# alimentation.net
KiCad netlist of a schematic drawn in Altium Designer
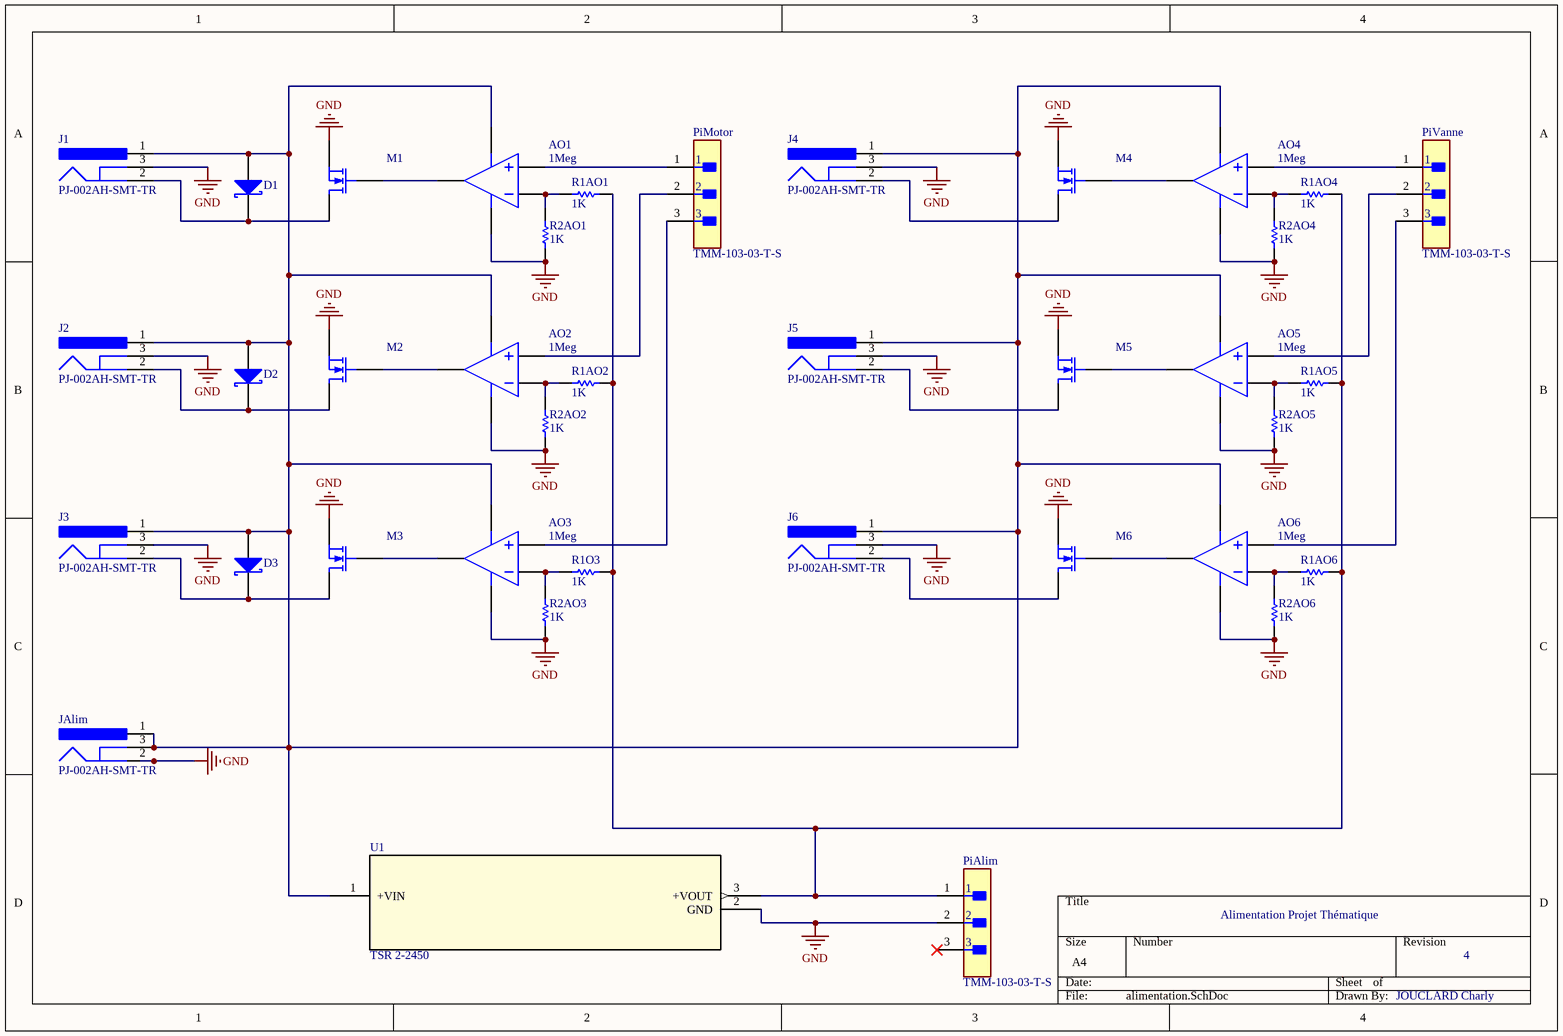
[diagram p0: alimentation.SchDoc]

(export (version "E")
  (design (tool "Eeschema 10.0.6"))
  (components
    (comp (ref "AO1")
      (value "Ideal Operational Amplifier")
      (fields (field (name "GAIN") "1Meg"))
      (libsource (lib "Simulation Generic Components") (part "OpAmp with power terminals"))
    )
    (comp (ref "AO2")
      (value "Ideal Operational Amplifier")
      (fields (field (name "GAIN") "1Meg"))
      (libsource (lib "Simulation Generic Components") (part "OpAmp with power terminals"))
    )
    (comp (ref "AO3")
      (value "Ideal Operational Amplifier")
      (fields (field (name "GAIN") "1Meg"))
      (libsource (lib "Simulation Generic Components") (part "OpAmp with power terminals"))
    )
    (comp (ref "AO4")
      (value "Ideal Operational Amplifier")
      (fields (field (name "GAIN") "1Meg"))
      (libsource (lib "Simulation Generic Components") (part "OpAmp with power terminals"))
    )
    (comp (ref "AO5")
      (value "Ideal Operational Amplifier")
      (fields (field (name "GAIN") "1Meg"))
      (libsource (lib "Simulation Generic Components") (part "OpAmp with power terminals"))
    )
    (comp (ref "AO6")
      (value "Ideal Operational Amplifier")
      (fields (field (name "GAIN") "1Meg"))
      (libsource (lib "Simulation Generic Components") (part "OpAmp with power terminals"))
    )
    (comp (ref "D1")
      (value "Shottky Diode")
      (libsource (lib "Simulation Generic Components") (part "Shottky Diode"))
    )
    (comp (ref "D2")
      (value "Shottky Diode")
      (libsource (lib "Simulation Generic Components") (part "Shottky Diode"))
    )
    (comp (ref "D3")
      (value "Shottky Diode")
      (libsource (lib "Simulation Generic Components") (part "Shottky Diode"))
    )
    (comp (ref "J1")
      (value "PJ-002AH-SMT-TR")
      (footprint "CUI-PJ-002AH-4_V")
      (description "DC Power Jack, Right Angle, -25 to 85 degC, 4-Pin 14.8 x 9 x 11 mm SMD, RoHS, Tape and Reel")
      (fields (field (name "MANUFACTURER") "CUIInc.") (field (name "PARTNUMBER") "PJ-002AH"))
      (libsource (lib "Altium Content Vault") (part "JACK-2CD3-RN_B"))
    )
    (comp (ref "J2")
      (value "PJ-002AH-SMT-TR")
      (footprint "CUI-PJ-002AH-4_V")
      (description "DC Power Jack, Right Angle, -25 to 85 degC, 4-Pin 14.8 x 9 x 11 mm SMD, RoHS, Tape and Reel")
      (fields (field (name "MANUFACTURER") "CUIInc.") (field (name "PARTNUMBER") "PJ-002AH"))
      (libsource (lib "Altium Content Vault") (part "JACK-2CD3-RN_B"))
    )
    (comp (ref "J3")
      (value "PJ-002AH-SMT-TR")
      (footprint "CUI-PJ-002AH-4_V")
      (description "DC Power Jack, Right Angle, -25 to 85 degC, 4-Pin 14.8 x 9 x 11 mm SMD, RoHS, Tape and Reel")
      (fields (field (name "MANUFACTURER") "CUIInc.") (field (name "PARTNUMBER") "PJ-002AH"))
      (libsource (lib "Altium Content Vault") (part "JACK-2CD3-RN_B"))
    )
    (comp (ref "J4")
      (value "PJ-002AH-SMT-TR")
      (footprint "CUI-PJ-002AH-4_V")
      (description "DC Power Jack, Right Angle, -25 to 85 degC, 4-Pin 14.8 x 9 x 11 mm SMD, RoHS, Tape and Reel")
      (fields (field (name "MANUFACTURER") "CUIInc.") (field (name "PARTNUMBER") "PJ-002AH"))
      (libsource (lib "Altium Content Vault") (part "JACK-2CD3-RN_B"))
    )
    (comp (ref "J5")
      (value "PJ-002AH-SMT-TR")
      (footprint "CUI-PJ-002AH-4_V")
      (description "DC Power Jack, Right Angle, -25 to 85 degC, 4-Pin 14.8 x 9 x 11 mm SMD, RoHS, Tape and Reel")
      (fields (field (name "MANUFACTURER") "CUIInc.") (field (name "PARTNUMBER") "PJ-002AH"))
      (libsource (lib "Altium Content Vault") (part "JACK-2CD3-RN_B"))
    )
    (comp (ref "J6")
      (value "PJ-002AH-SMT-TR")
      (footprint "CUI-PJ-002AH-4_V")
      (description "DC Power Jack, Right Angle, -25 to 85 degC, 4-Pin 14.8 x 9 x 11 mm SMD, RoHS, Tape and Reel")
      (fields (field (name "MANUFACTURER") "CUIInc.") (field (name "PARTNUMBER") "PJ-002AH"))
      (libsource (lib "Altium Content Vault") (part "JACK-2CD3-RN_B"))
    )
    (comp (ref "JAlim")
      (value "PJ-002AH-SMT-TR")
      (footprint "CUI-PJ-002AH-4_V")
      (description "DC Power Jack, Right Angle, -25 to 85 degC, 4-Pin 14.8 x 9 x 11 mm SMD, RoHS, Tape and Reel")
      (fields (field (name "MANUFACTURER") "CUIInc.") (field (name "PARTNUMBER") "PJ-002AH"))
      (libsource (lib "Altium Content Vault") (part "JACK-2CD3-RN_B"))
    )
    (comp (ref "M1")
      (value "N-chanel Power MOSFET VDMOS Model")
      (description "MOSFET CSD18537NKCS")
      (libsource (lib "Simulation Generic Components") (part "MOSFET N-ch VDMOS"))
    )
    (comp (ref "M2")
      (value "N-chanel Power MOSFET VDMOS Model")
      (description "MOSFET CSD18537NKCS")
      (libsource (lib "Simulation Generic Components") (part "MOSFET N-ch VDMOS"))
    )
    (comp (ref "M3")
      (value "N-chanel Power MOSFET VDMOS Model")
      (description "MOSFET CSD18537NKCS")
      (libsource (lib "Simulation Generic Components") (part "MOSFET N-ch VDMOS"))
    )
    (comp (ref "M4")
      (value "N-chanel Power MOSFET VDMOS Model")
      (description "MOSFET CSD18537NKCS")
      (libsource (lib "Simulation Generic Components") (part "MOSFET N-ch VDMOS"))
    )
    (comp (ref "M5")
      (value "N-chanel Power MOSFET VDMOS Model")
      (description "MOSFET CSD18537NKCS")
      (libsource (lib "Simulation Generic Components") (part "MOSFET N-ch VDMOS"))
    )
    (comp (ref "M6")
      (value "N-chanel Power MOSFET VDMOS Model")
      (description "MOSFET CSD18537NKCS")
      (libsource (lib "Simulation Generic Components") (part "MOSFET N-ch VDMOS"))
    )
    (comp (ref "PiAlim")
      (value "TMM-103-03-T-S")
      (footprint "FP-TMM-103-03-T-S-MFG")
      (description "CONN HEADER VERT 3POS 2MM")
      (libsource (lib "Altium Content Vault") (part "0d3f023dd272f625e17a2be33dea85f"))
    )
    (comp (ref "PiMotor")
      (value "TMM-103-03-T-S")
      (footprint "FP-TMM-103-03-T-S-MFG")
      (description "CONN HEADER VERT 3POS 2MM")
      (libsource (lib "Altium Content Vault") (part "0d3f023dd272f625e17a2be33dea85f"))
    )
    (comp (ref "PiVanne")
      (value "TMM-103-03-T-S")
      (footprint "FP-TMM-103-03-T-S-MFG")
      (description "CONN HEADER VERT 3POS 2MM")
      (libsource (lib "Altium Content Vault") (part "0d3f023dd272f625e17a2be33dea85f"))
    )
    (comp (ref "R1AO1")
      (value "1K")
      (description "Resistor")
      (libsource (lib "Simulation Generic Components") (part "Resistor"))
    )
    (comp (ref "R1AO2")
      (value "1K")
      (description "Resistor")
      (libsource (lib "Simulation Generic Components") (part "Resistor"))
    )
    (comp (ref "R1AO4")
      (value "1K")
      (description "Resistor")
      (libsource (lib "Simulation Generic Components") (part "Resistor"))
    )
    (comp (ref "R1AO5")
      (value "1K")
      (description "Resistor")
      (libsource (lib "Simulation Generic Components") (part "Resistor"))
    )
    (comp (ref "R1AO6")
      (value "1K")
      (description "Resistor")
      (libsource (lib "Simulation Generic Components") (part "Resistor"))
    )
    (comp (ref "R1O3")
      (value "1K")
      (description "Resistor")
      (libsource (lib "Simulation Generic Components") (part "Resistor"))
    )
    (comp (ref "R2AO1")
      (value "1K")
      (description "Resistor")
      (libsource (lib "Simulation Generic Components") (part "Resistor"))
    )
    (comp (ref "R2AO2")
      (value "1K")
      (description "Resistor")
      (libsource (lib "Simulation Generic Components") (part "Resistor"))
    )
    (comp (ref "R2AO3")
      (value "1K")
      (description "Resistor")
      (libsource (lib "Simulation Generic Components") (part "Resistor"))
    )
    (comp (ref "R2AO4")
      (value "1K")
      (description "Resistor")
      (libsource (lib "Simulation Generic Components") (part "Resistor"))
    )
    (comp (ref "R2AO5")
      (value "1K")
      (description "Resistor")
      (libsource (lib "Simulation Generic Components") (part "Resistor"))
    )
    (comp (ref "R2AO6")
      (value "1K")
      (description "Resistor")
      (libsource (lib "Simulation Generic Components") (part "Resistor"))
    )
    (comp (ref "U1")
      (value "TSR 2-2450")
      (footprint "TSR 2-2450_TRP")
      (description "DC DC CONVERTER 5V 10W")
      (libsource (lib "Altium Content Vault") (part "TSR 2-2450"))
    )
  )
  (nets
    (net (code "1") (name "GND") (class "Default")
      (node (ref "AO1") (pin "4") (pinfunction "V+_4") (pintype "power_in"))
      (node (ref "AO2") (pin "4") (pinfunction "V+_4") (pintype "power_in"))
      (node (ref "AO3") (pin "4") (pinfunction "V+_4") (pintype "power_in"))
      (node (ref "AO4") (pin "4") (pinfunction "V+_4") (pintype "power_in"))
      (node (ref "AO5") (pin "4") (pinfunction "V+_4") (pintype "power_in"))
      (node (ref "AO6") (pin "4") (pinfunction "V+_4") (pintype "power_in"))
      (node (ref "J1") (pin "3") (pinfunction "3_3") (pintype "passive"))
      (node (ref "J2") (pin "3") (pinfunction "3_3") (pintype "passive"))
      (node (ref "J3") (pin "3") (pinfunction "3_3") (pintype "passive"))
      (node (ref "J4") (pin "3") (pinfunction "3_3") (pintype "passive"))
      (node (ref "J5") (pin "3") (pinfunction "3_3") (pintype "passive"))
      (node (ref "J6") (pin "3") (pinfunction "3_3") (pintype "passive"))
      (node (ref "JAlim") (pin "2") (pinfunction "2_2") (pintype "passive"))
      (node (ref "M1") (pin "3") (pinfunction "S_3") (pintype "passive"))
      (node (ref "M2") (pin "3") (pinfunction "S_3") (pintype "passive"))
      (node (ref "M3") (pin "3") (pinfunction "S_3") (pintype "passive"))
      (node (ref "M4") (pin "3") (pinfunction "S_3") (pintype "passive"))
      (node (ref "M5") (pin "3") (pinfunction "S_3") (pintype "passive"))
      (node (ref "M6") (pin "3") (pinfunction "S_3") (pintype "passive"))
      (node (ref "PiAlim") (pin "2") (pinfunction "2_2") (pintype "passive"))
      (node (ref "R2AO1") (pin "1") (pinfunction "1_1") (pintype "passive"))
      (node (ref "R2AO2") (pin "1") (pinfunction "1_1") (pintype "passive"))
      (node (ref "R2AO3") (pin "1") (pinfunction "1_1") (pintype "passive"))
      (node (ref "R2AO4") (pin "1") (pinfunction "1_1") (pintype "passive"))
      (node (ref "R2AO5") (pin "1") (pinfunction "1_1") (pintype "passive"))
      (node (ref "R2AO6") (pin "1") (pinfunction "1_1") (pintype "passive"))
      (node (ref "U1") (pin "2") (pinfunction "GND_2") (pintype "power_in"))
    )
    (net (code "2") (name "Net-(AO1-IN+)") (class "Default")
      (node (ref "AO1") (pin "2") (pinfunction "IN+_2") (pintype "passive"))
      (node (ref "PiMotor") (pin "1") (pinfunction "1_1") (pintype "passive"))
    )
    (net (code "3") (name "Net-(AO1-IN-)") (class "Default")
      (node (ref "AO1") (pin "1") (pinfunction "IN-_1") (pintype "passive"))
      (node (ref "R1AO1") (pin "1") (pinfunction "1_1") (pintype "passive"))
      (node (ref "R2AO1") (pin "2") (pinfunction "2_2") (pintype "passive"))
    )
    (net (code "4") (name "Net-(AO1-OUT)") (class "Default")
      (node (ref "AO1") (pin "3") (pinfunction "OUT_3") (pintype "passive"))
      (node (ref "M1") (pin "2") (pinfunction "G_2") (pintype "passive"))
    )
    (net (code "5") (name "Net-(AO1-V-)") (class "Default")
      (node (ref "AO1") (pin "5") (pinfunction "V-_5") (pintype "power_in"))
      (node (ref "AO2") (pin "5") (pinfunction "V-_5") (pintype "power_in"))
      (node (ref "AO3") (pin "5") (pinfunction "V-_5") (pintype "power_in"))
      (node (ref "AO4") (pin "5") (pinfunction "V-_5") (pintype "power_in"))
      (node (ref "AO5") (pin "5") (pinfunction "V-_5") (pintype "power_in"))
      (node (ref "AO6") (pin "5") (pinfunction "V-_5") (pintype "power_in"))
      (node (ref "D1") (pin "1") (pinfunction "A_1") (pintype "passive"))
      (node (ref "D2") (pin "1") (pinfunction "A_1") (pintype "passive"))
      (node (ref "D3") (pin "1") (pinfunction "A_1") (pintype "passive"))
      (node (ref "J1") (pin "1") (pinfunction "1_1") (pintype "passive"))
      (node (ref "J2") (pin "1") (pinfunction "1_1") (pintype "passive"))
      (node (ref "J3") (pin "1") (pinfunction "1_1") (pintype "passive"))
      (node (ref "J4") (pin "1") (pinfunction "1_1") (pintype "passive"))
      (node (ref "J5") (pin "1") (pinfunction "1_1") (pintype "passive"))
      (node (ref "J6") (pin "1") (pinfunction "1_1") (pintype "passive"))
      (node (ref "JAlim") (pin "1") (pinfunction "1_1") (pintype "passive"))
      (node (ref "JAlim") (pin "3") (pinfunction "3_3") (pintype "passive"))
      (node (ref "U1") (pin "1") (pinfunction "+VIN_1") (pintype "power_in"))
    )
    (net (code "6") (name "Net-(AO2-IN+)") (class "Default")
      (node (ref "AO2") (pin "2") (pinfunction "IN+_2") (pintype "passive"))
      (node (ref "PiMotor") (pin "2") (pinfunction "2_2") (pintype "passive"))
    )
    (net (code "7") (name "Net-(AO2-IN-)") (class "Default")
      (node (ref "AO2") (pin "1") (pinfunction "IN-_1") (pintype "passive"))
      (node (ref "R1AO2") (pin "1") (pinfunction "1_1") (pintype "passive"))
      (node (ref "R2AO2") (pin "2") (pinfunction "2_2") (pintype "passive"))
    )
    (net (code "8") (name "Net-(AO2-OUT)") (class "Default")
      (node (ref "AO2") (pin "3") (pinfunction "OUT_3") (pintype "passive"))
      (node (ref "M2") (pin "2") (pinfunction "G_2") (pintype "passive"))
    )
    (net (code "9") (name "Net-(AO3-IN+)") (class "Default")
      (node (ref "AO3") (pin "2") (pinfunction "IN+_2") (pintype "passive"))
      (node (ref "PiMotor") (pin "3") (pinfunction "3_3") (pintype "passive"))
    )
    (net (code "10") (name "Net-(AO3-IN-)") (class "Default")
      (node (ref "AO3") (pin "1") (pinfunction "IN-_1") (pintype "passive"))
      (node (ref "R1O3") (pin "1") (pinfunction "1_1") (pintype "passive"))
      (node (ref "R2AO3") (pin "2") (pinfunction "2_2") (pintype "passive"))
    )
    (net (code "11") (name "Net-(AO3-OUT)") (class "Default")
      (node (ref "AO3") (pin "3") (pinfunction "OUT_3") (pintype "passive"))
      (node (ref "M3") (pin "2") (pinfunction "G_2") (pintype "passive"))
    )
    (net (code "12") (name "Net-(AO4-IN+)") (class "Default")
      (node (ref "AO4") (pin "2") (pinfunction "IN+_2") (pintype "passive"))
      (node (ref "PiVanne") (pin "1") (pinfunction "1_1") (pintype "passive"))
    )
    (net (code "13") (name "Net-(AO4-IN-)") (class "Default")
      (node (ref "AO4") (pin "1") (pinfunction "IN-_1") (pintype "passive"))
      (node (ref "R1AO4") (pin "1") (pinfunction "1_1") (pintype "passive"))
      (node (ref "R2AO4") (pin "2") (pinfunction "2_2") (pintype "passive"))
    )
    (net (code "14") (name "Net-(AO4-OUT)") (class "Default")
      (node (ref "AO4") (pin "3") (pinfunction "OUT_3") (pintype "passive"))
      (node (ref "M4") (pin "2") (pinfunction "G_2") (pintype "passive"))
    )
    (net (code "15") (name "Net-(AO5-IN+)") (class "Default")
      (node (ref "AO5") (pin "2") (pinfunction "IN+_2") (pintype "passive"))
      (node (ref "PiVanne") (pin "2") (pinfunction "2_2") (pintype "passive"))
    )
    (net (code "16") (name "Net-(AO5-IN-)") (class "Default")
      (node (ref "AO5") (pin "1") (pinfunction "IN-_1") (pintype "passive"))
      (node (ref "R1AO5") (pin "1") (pinfunction "1_1") (pintype "passive"))
      (node (ref "R2AO5") (pin "2") (pinfunction "2_2") (pintype "passive"))
    )
    (net (code "17") (name "Net-(AO5-OUT)") (class "Default")
      (node (ref "AO5") (pin "3") (pinfunction "OUT_3") (pintype "passive"))
      (node (ref "M5") (pin "2") (pinfunction "G_2") (pintype "passive"))
    )
    (net (code "18") (name "Net-(AO6-IN+)") (class "Default")
      (node (ref "AO6") (pin "2") (pinfunction "IN+_2") (pintype "passive"))
      (node (ref "PiVanne") (pin "3") (pinfunction "3_3") (pintype "passive"))
    )
    (net (code "19") (name "Net-(AO6-IN-)") (class "Default")
      (node (ref "AO6") (pin "1") (pinfunction "IN-_1") (pintype "passive"))
      (node (ref "R1AO6") (pin "1") (pinfunction "1_1") (pintype "passive"))
      (node (ref "R2AO6") (pin "2") (pinfunction "2_2") (pintype "passive"))
    )
    (net (code "20") (name "Net-(AO6-OUT)") (class "Default")
      (node (ref "AO6") (pin "3") (pinfunction "OUT_3") (pintype "passive"))
      (node (ref "M6") (pin "2") (pinfunction "G_2") (pintype "passive"))
    )
    (net (code "21") (name "Net-(D1-K)") (class "Default")
      (node (ref "D1") (pin "2") (pinfunction "K_2") (pintype "passive"))
      (node (ref "J1") (pin "2") (pinfunction "2_2") (pintype "passive"))
      (node (ref "M1") (pin "1") (pinfunction "D_1") (pintype "passive"))
    )
    (net (code "22") (name "Net-(D2-K)") (class "Default")
      (node (ref "D2") (pin "2") (pinfunction "K_2") (pintype "passive"))
      (node (ref "J2") (pin "2") (pinfunction "2_2") (pintype "passive"))
      (node (ref "M2") (pin "1") (pinfunction "D_1") (pintype "passive"))
    )
    (net (code "23") (name "Net-(D3-K)") (class "Default")
      (node (ref "D3") (pin "2") (pinfunction "K_2") (pintype "passive"))
      (node (ref "J3") (pin "2") (pinfunction "2_2") (pintype "passive"))
      (node (ref "M3") (pin "1") (pinfunction "D_1") (pintype "passive"))
    )
    (net (code "24") (name "Net-(M4-D)") (class "Default")
      (node (ref "J4") (pin "2") (pinfunction "2_2") (pintype "passive"))
      (node (ref "M4") (pin "1") (pinfunction "D_1") (pintype "passive"))
    )
    (net (code "25") (name "Net-(M5-D)") (class "Default")
      (node (ref "J5") (pin "2") (pinfunction "2_2") (pintype "passive"))
      (node (ref "M5") (pin "1") (pinfunction "D_1") (pintype "passive"))
    )
    (net (code "26") (name "Net-(M6-D)") (class "Default")
      (node (ref "J6") (pin "2") (pinfunction "2_2") (pintype "passive"))
      (node (ref "M6") (pin "1") (pinfunction "D_1") (pintype "passive"))
    )
    (net (code "27") (name "Net-(U1-+VOUT)") (class "Default")
      (node (ref "PiAlim") (pin "1") (pinfunction "1_1") (pintype "passive"))
      (node (ref "R1AO1") (pin "2") (pinfunction "2_2") (pintype "passive"))
      (node (ref "R1AO2") (pin "2") (pinfunction "2_2") (pintype "passive"))
      (node (ref "R1AO4") (pin "2") (pinfunction "2_2") (pintype "passive"))
      (node (ref "R1AO5") (pin "2") (pinfunction "2_2") (pintype "passive"))
      (node (ref "R1AO6") (pin "2") (pinfunction "2_2") (pintype "passive"))
      (node (ref "R1O3") (pin "2") (pinfunction "2_2") (pintype "passive"))
      (node (ref "U1") (pin "3") (pinfunction "+VOUT_3") (pintype "output"))
    )
    (net (code "28") (name "unconnected-(PiAlim-Pad3)") (class "Default")
      (node (ref "PiAlim") (pin "3") (pinfunction "3_3") (pintype "passive+no_connect"))
    )
  )
)
